# WE_1100_top.net
KiCad netlist of a schematic drawn in Altium Designer
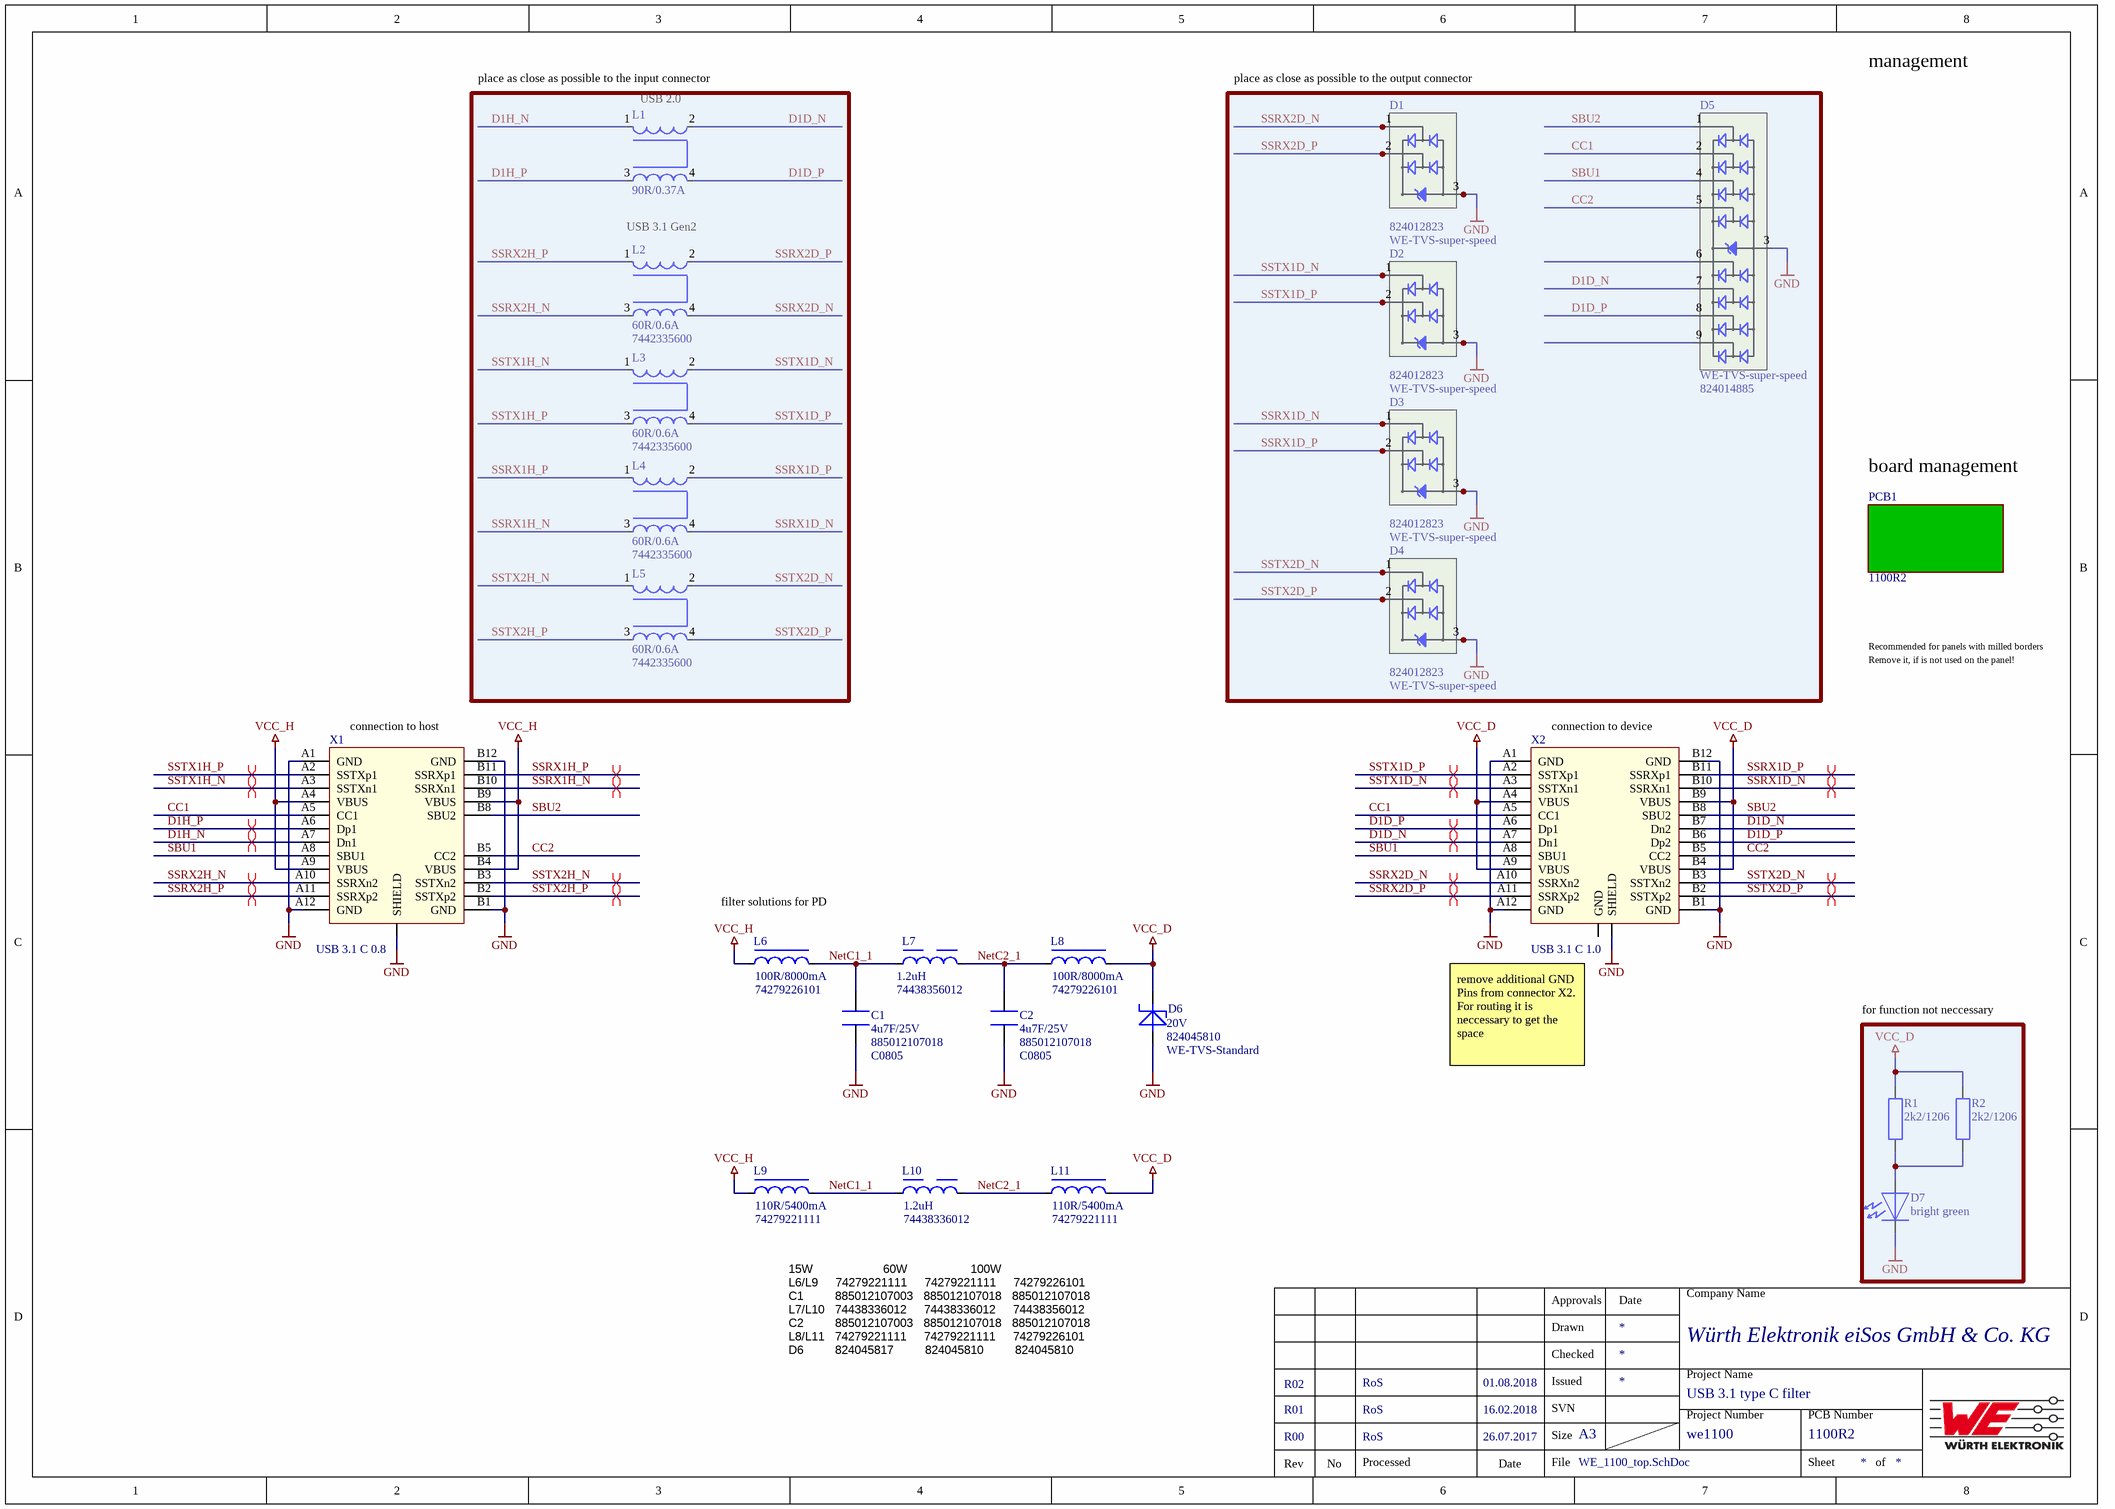
[diagram p0: WE_1100_top.SchDoc]

(export (version "E")
  (design (tool "Eeschema 10.0.6"))
  (components
    (comp (ref "C1")
      (value "4u7F/25V")
      (footprint "C0805 (reflow)")
      (description "Ceramic SMT X5R 4,7uF/25V 0805")
      (fields
        (field (name "ART.-CODE") "885012107018")
        (field (name "MANUFACTURER") "WE")
        (field (name "TOLERANCE") "20%")
        (field (name "CASE") "C0805")
      )
      (libsource (lib "capacitor") (part "4UF7/25-X5R-0805"))
    )
    (comp (ref "C2")
      (value "4u7F/25V")
      (footprint "C0805 (reflow)")
      (description "Ceramic SMT X5R 4,7uF/25V 0805")
      (fields
        (field (name "ART.-CODE") "885012107018")
        (field (name "MANUFACTURER") "WE")
        (field (name "TOLERANCE") "20%")
        (field (name "CASE") "C0805")
      )
      (libsource (lib "capacitor") (part "4UF7/25-X5R-0805"))
    )
    (comp (ref "D1")
      (value "WE-TVS-super-speed")
      (footprint "DFN88P100X50-6L")
      (description "TVS, diode, array, 2 channel ESD protection, 3.3V, DFN1012-6")
      (fields
        (field (name "MANUFACTURER") "WE")
        (field (name "VOLTAGE") "3.3V")
        (field (name "PART-NO.") "824012823")
      )
      (libsource (lib "rectifier") (part "WE-TVS-ULC-DFN1012-6"))
    )
    (comp (ref "D2")
      (value "WE-TVS-super-speed")
      (footprint "DFN88P100X50-6L")
      (description "TVS, diode, array, 2 channel ESD protection, 3.3V, DFN1012-6")
      (fields
        (field (name "MANUFACTURER") "WE")
        (field (name "VOLTAGE") "3.3V")
        (field (name "PART-NO.") "824012823")
      )
      (libsource (lib "rectifier") (part "WE-TVS-ULC-DFN1012-6"))
    )
    (comp (ref "D3")
      (value "WE-TVS-super-speed")
      (footprint "DFN88P100X50-6L")
      (description "TVS, diode, array, 2 channel ESD protection, 3.3V, DFN1012-6")
      (fields
        (field (name "MANUFACTURER") "WE")
        (field (name "VOLTAGE") "3.3V")
        (field (name "PART-NO.") "824012823")
      )
      (libsource (lib "rectifier") (part "WE-TVS-ULC-DFN1012-6"))
    )
    (comp (ref "D4")
      (value "WE-TVS-super-speed")
      (footprint "DFN88P100X50-6L")
      (description "TVS, diode, array, 2 channel ESD protection, 3.3V, DFN1012-6")
      (fields
        (field (name "MANUFACTURER") "WE")
        (field (name "VOLTAGE") "3.3V")
        (field (name "PART-NO.") "824012823")
      )
      (libsource (lib "rectifier") (part "WE-TVS-ULC-DFN1012-6"))
    )
    (comp (ref "D5")
      (value "WE-TVS-super-speed")
      (footprint "DFN90P380X55-9L")
      (description "TVS, diode, array, 8 channel ESD protection, 1.2V, DFN3810-9")
      (fields
        (field (name "MANUFACTURER") "WE")
        (field (name "VOLTAGE") "1.2V")
        (field (name "PART-NO.") "824014885")
      )
      (libsource (lib "rectifier") (part "WE-TVS-ULC-DFN3810"))
    )
    (comp (ref "D6")
      (value "WE-TVS-Standard")
      (footprint "DFN110P160X55-2L")
      (description "TVS, diode, unidir, ESD protection, 20V, DFN1610")
      (fields
        (field (name "MANUFACTURER") "WE")
        (field (name "VOLTAGE") "20V")
        (field (name "PART-NO.") "824045810")
      )
      (libsource (lib "rectifier") (part "WE-TVS20-ULC-DFN1610"))
    )
    (comp (ref "D7")
      (value "bright green")
      (footprint "LED-SMD-GR-2014X09L")
      (description "SMD-LED, Chipled 0805, brigth green")
      (fields (field (name "MANUFACTURER") "WE") (field (name "VOLTAGE") "2.0V"))
      (libsource (lib "optoelectronic") (part "LED Chipled VS 0805"))
    )
    (comp (ref "L1")
      (value "90R/0.37A")
      (footprint "WE-CNSW-0805 (REFLOW)")
      (description "Common mode line filter SMD WE-CNSW (USB, LVDS)")
      (fields
        (field (name "MANUFACTURER") "WE")
        (field (name "TOLERANCE") "25%")
        (field (name "HELPURL") "d:\\Hardware\\Datasheet\\Induktivitäten\\WE-CNSW\\744231091.pdf")
      )
      (libsource (lib "inductance") (part "Z90R-370mA-WE-CNSW"))
    )
    (comp (ref "L2")
      (value "60R/0.6A")
      (footprint "WE-CNSW-HF-0504 (REFLOW)")
      (description "Common mode line filter SMD WE-CNSW HF (USB3.0)")
      (fields
        (field (name "MANUFACTURER") "WE")
        (field (name "TOLERANCE") "25%")
        (field (name "PART-NO.") "7442335600")
        (field (name "HELPURL") "d:\\Hardware\\Datasheet\\Induktivitäten\\WE-CNSW_HF\\7442335600.pdf")
      )
      (libsource (lib "inductance") (part "Z60R-600mA-WE-CNSW HF"))
    )
    (comp (ref "L3")
      (value "60R/0.6A")
      (footprint "WE-CNSW-HF-0504 (REFLOW)")
      (description "Common mode line filter SMD WE-CNSW HF (USB3.0)")
      (fields
        (field (name "MANUFACTURER") "WE")
        (field (name "TOLERANCE") "25%")
        (field (name "PART-NO.") "7442335600")
        (field (name "HELPURL") "d:\\Hardware\\Datasheet\\Induktivitäten\\WE-CNSW_HF\\7442335600.pdf")
      )
      (libsource (lib "inductance") (part "Z60R-600mA-WE-CNSW HF"))
    )
    (comp (ref "L4")
      (value "60R/0.6A")
      (footprint "WE-CNSW-HF-0504 (REFLOW)")
      (description "Common mode line filter SMD WE-CNSW HF (USB3.0)")
      (fields
        (field (name "MANUFACTURER") "WE")
        (field (name "TOLERANCE") "25%")
        (field (name "PART-NO.") "7442335600")
        (field (name "HELPURL") "d:\\Hardware\\Datasheet\\Induktivitäten\\WE-CNSW_HF\\7442335600.pdf")
      )
      (libsource (lib "inductance") (part "Z60R-600mA-WE-CNSW HF"))
    )
    (comp (ref "L5")
      (value "60R/0.6A")
      (footprint "WE-CNSW-HF-0504 (REFLOW)")
      (description "Common mode line filter SMD WE-CNSW HF (USB3.0)")
      (fields
        (field (name "MANUFACTURER") "WE")
        (field (name "TOLERANCE") "25%")
        (field (name "PART-NO.") "7442335600")
        (field (name "HELPURL") "d:\\Hardware\\Datasheet\\Induktivitäten\\WE-CNSW_HF\\7442335600.pdf")
      )
      (libsource (lib "inductance") (part "Z60R-600mA-WE-CNSW HF"))
    )
    (comp (ref "L6")
      (value "100R/8000mA")
      (footprint "WE-MPSB_1812")
      (description "Multilayer Power Suppression Bead 1812 100R at 100MHz/0.006R")
      (fields
        (field (name "ART.-CODE") "74279226101")
        (field (name "MANUFACTURER") "WE")
        (field (name "TOLERANCE") "25%")
        (field (name "HELPURL") "d:\\Hardware\\Datasheet\\Induktivitäten\\Ferrit\\74279226101.pdf")
      )
      (libsource (lib "inductance") (part "Z100R_8000mA_1812_MPSB"))
    )
    (comp (ref "L7")
      (value "1.2uH")
      (footprint "WE-MAPI_4020")
      (description "Inductor SMT WE-MAPI 4020 1.2uH/5800mA")
      (fields
        (field (name "MANUFACTURER") "WE")
        (field (name "ART.-CODE") "74438356012")
        (field (name "TOLERANCE") "20%")
        (field (name "HELPURL") "d:\\Hardware\\Datasheet\\Induktivitäten\\WE-MAPI\\74438356012.pdf")
      )
      (libsource (lib "inductance") (part "1UH2-5.8A-SMD-WE-MAPI 4020"))
    )
    (comp (ref "L8")
      (value "100R/8000mA")
      (footprint "WE-MPSB_1812")
      (description "Multilayer Power Suppression Bead 1812 100R at 100MHz/0.006R")
      (fields
        (field (name "ART.-CODE") "74279226101")
        (field (name "MANUFACTURER") "WE")
        (field (name "TOLERANCE") "25%")
        (field (name "HELPURL") "d:\\Hardware\\Datasheet\\Induktivitäten\\Ferrit\\74279226101.pdf")
      )
      (libsource (lib "inductance") (part "Z100R_8000mA_1812_MPSB"))
    )
    (comp (ref "L9")
      (value "110R/5400mA")
      (footprint "WE-MPSB_1206")
      (description "Multilayer Power Suppression Bead 1206 110R at 100MHz/0.0095R")
      (fields
        (field (name "ART.-CODE") "74279221111")
        (field (name "MANUFACTURER") "WE")
        (field (name "TOLERANCE") "25%")
        (field (name "HELPURL") "d:\\Hardware\\Datasheet\\Induktivitäten\\Ferrit\\74279221111.pdf")
      )
      (libsource (lib "inductance") (part "Z110R_5400mA_1206_MPSB"))
    )
    (comp (ref "L10")
      (value "1.2uH")
      (footprint "WE-MAPI_3020")
      (description "Inductor SMT WE-MAPI 3020 1.2uH/3900mA")
      (fields
        (field (name "MANUFACTURER") "WE")
        (field (name "ART.-CODE") "74438336012")
        (field (name "TOLERANCE") "20%")
        (field (name "HELPURL") "d:\\Hardware\\Datasheet\\Induktivitäten\\WE-MAPI\\74438336012.pdf")
      )
      (libsource (lib "inductance") (part "1UH2-3.9A-SMD-WE-MAPI 3020"))
    )
    (comp (ref "L11")
      (value "110R/5400mA")
      (footprint "WE-MPSB_1206")
      (description "Multilayer Power Suppression Bead 1206 110R at 100MHz/0.0095R")
      (fields
        (field (name "ART.-CODE") "74279221111")
        (field (name "MANUFACTURER") "WE")
        (field (name "TOLERANCE") "25%")
        (field (name "HELPURL") "d:\\Hardware\\Datasheet\\Induktivitäten\\Ferrit\\74279221111.pdf")
      )
      (libsource (lib "inductance") (part "Z110R_5400mA_1206_MPSB"))
    )
    (comp (ref "PCB1")
      (value "1100R2")
      (description "only for partlist")
      (libsource (lib "misc") (part "PCB"))
    )
    (comp (ref "R1")
      (value "2k2/1206")
      (footprint "R1206 (reflow)")
      (description "Resistor 2K2 1% 1206 E24")
      (fields (field (name "POWER") "1/4W") (field (name "TOLERANCE") "1%"))
      (libsource (lib "resistor") (part "2K2-1-1206"))
    )
    (comp (ref "R2")
      (value "2k2/1206")
      (footprint "R1206 (reflow)")
      (description "Resistor 2K2 1% 1206 E24")
      (fields (field (name "POWER") "1/4W") (field (name "TOLERANCE") "1%"))
      (libsource (lib "resistor") (part "2K2-1-1206"))
    )
    (comp (ref "X1")
      (value "USB 3.1 C 0.8")
      (footprint "632712000011")
      (description "male USB 3.1 Type C 24 pins 90° THT & SMT LP 0.8")
      (fields (field (name "MANUFACTURER") "WE") (field (name "VOLTAGE") "20V"))
      (libsource (lib "connector") (part "ST-24 USB 3.1 C 0.8"))
    )
    (comp (ref "X2")
      (value "USB 3.1 C 1.0")
      (footprint "632723100011")
      (description "female USB 3.1 Type C 24 pins 90° THT & SMT LP 1.0")
      (fields (field (name "MANUFACTURER") "WE") (field (name "VOLTAGE") "20V"))
      (libsource (lib "connector") (part "BU-24 USB 3.1 C 1.0"))
    )
  )
  (nets
    (net (code "1") (name "/CC1") (class "Default")
      (node (ref "D5") (pin "2") (pinfunction "I/O2_2") (pintype "passive"))
      (node (ref "X1") (pin "A5") (pinfunction "CC1_A5") (pintype "passive"))
      (node (ref "X2") (pin "A5") (pinfunction "CC1_A5") (pintype "passive"))
    )
    (net (code "2") (name "/CC2") (class "Default")
      (node (ref "D5") (pin "5") (pinfunction "I/O4_5") (pintype "passive"))
      (node (ref "X1") (pin "B5") (pinfunction "CC2_B5") (pintype "passive"))
      (node (ref "X2") (pin "B5") (pinfunction "CC2_B5") (pintype "passive"))
    )
    (net (code "3") (name "/D1D_N") (class "Default")
      (node (ref "D5") (pin "7") (pinfunction "NC_7") (pintype "passive"))
      (node (ref "L1") (pin "2") (pintype "passive"))
      (node (ref "X2") (pin "A7") (pinfunction "Dn1_A7") (pintype "passive"))
      (node (ref "X2") (pin "B7") (pinfunction "Dn2_B7") (pintype "passive"))
    )
    (net (code "4") (name "/D1D_P") (class "Default")
      (node (ref "D5") (pin "8") (pinfunction "GND_8") (pintype "passive"))
      (node (ref "L1") (pin "4") (pintype "passive"))
      (node (ref "X2") (pin "A6") (pinfunction "Dp1_A6") (pintype "passive"))
      (node (ref "X2") (pin "B6") (pinfunction "Dp2_B6") (pintype "passive"))
    )
    (net (code "5") (name "/D1H_N") (class "Default")
      (node (ref "L1") (pin "1") (pintype "passive"))
      (node (ref "X1") (pin "A7") (pinfunction "Dn1_A7") (pintype "passive"))
    )
    (net (code "6") (name "/D1H_P") (class "Default")
      (node (ref "L1") (pin "3") (pintype "passive"))
      (node (ref "X1") (pin "A6") (pinfunction "Dp1_A6") (pintype "passive"))
    )
    (net (code "7") (name "/NetC1_1") (class "Default")
      (node (ref "C1") (pin "1") (pintype "passive"))
      (node (ref "L10") (pin "1") (pintype "passive"))
      (node (ref "L6") (pin "2") (pintype "passive"))
      (node (ref "L7") (pin "1") (pintype "passive"))
      (node (ref "L9") (pin "2") (pintype "passive"))
    )
    (net (code "8") (name "/NetC2_1") (class "Default")
      (node (ref "C2") (pin "1") (pintype "passive"))
      (node (ref "L10") (pin "2") (pintype "passive"))
      (node (ref "L11") (pin "1") (pintype "passive"))
      (node (ref "L7") (pin "2") (pintype "passive"))
      (node (ref "L8") (pin "1") (pintype "passive"))
    )
    (net (code "9") (name "/SBU1") (class "Default")
      (node (ref "D5") (pin "4") (pinfunction "I/O3_4") (pintype "passive"))
      (node (ref "X1") (pin "A8") (pinfunction "SBU1_A8") (pintype "passive"))
      (node (ref "X2") (pin "A8") (pinfunction "SBU1_A8") (pintype "passive"))
    )
    (net (code "10") (name "/SBU2") (class "Default")
      (node (ref "D5") (pin "1") (pinfunction "I/O1_1") (pintype "passive"))
      (node (ref "X1") (pin "B8") (pinfunction "SBU2_B8") (pintype "passive"))
      (node (ref "X2") (pin "B8") (pinfunction "SBU2_B8") (pintype "passive"))
    )
    (net (code "11") (name "/SSRX1D_N") (class "Default")
      (node (ref "D3") (pin "1") (pinfunction "I/O1_1") (pintype "passive"))
      (node (ref "D3") (pin "6") (pinfunction "I/O1_6") (pintype "passive"))
      (node (ref "L4") (pin "4") (pintype "passive"))
      (node (ref "X2") (pin "B10") (pinfunction "SSRXn1_B10") (pintype "passive"))
    )
    (net (code "12") (name "/SSRX1D_P") (class "Default")
      (node (ref "D3") (pin "2") (pinfunction "I/O2_2") (pintype "passive"))
      (node (ref "D3") (pin "5") (pinfunction "I/O2_5") (pintype "passive"))
      (node (ref "L4") (pin "2") (pintype "passive"))
      (node (ref "X2") (pin "B11") (pinfunction "SSRXp1_B11") (pintype "passive"))
    )
    (net (code "13") (name "/SSRX1H_N") (class "Default")
      (node (ref "L4") (pin "3") (pintype "passive"))
      (node (ref "X1") (pin "B10") (pinfunction "SSRXn1_B10") (pintype "passive"))
    )
    (net (code "14") (name "/SSRX1H_P") (class "Default")
      (node (ref "L4") (pin "1") (pintype "passive"))
      (node (ref "X1") (pin "B11") (pinfunction "SSRXp1_B11") (pintype "passive"))
    )
    (net (code "15") (name "/SSRX2D_N") (class "Default")
      (node (ref "D1") (pin "1") (pinfunction "I/O1_1") (pintype "passive"))
      (node (ref "D1") (pin "6") (pinfunction "I/O1_6") (pintype "passive"))
      (node (ref "L2") (pin "4") (pintype "passive"))
      (node (ref "X2") (pin "A10") (pinfunction "SSRXn2_A10") (pintype "passive"))
    )
    (net (code "16") (name "/SSRX2D_P") (class "Default")
      (node (ref "D1") (pin "2") (pinfunction "I/O2_2") (pintype "passive"))
      (node (ref "D1") (pin "5") (pinfunction "I/O2_5") (pintype "passive"))
      (node (ref "L2") (pin "2") (pintype "passive"))
      (node (ref "X2") (pin "A11") (pinfunction "SSRXp2_A11") (pintype "passive"))
    )
    (net (code "17") (name "/SSRX2H_N") (class "Default")
      (node (ref "L2") (pin "3") (pintype "passive"))
      (node (ref "X1") (pin "A10") (pinfunction "SSRXn2_A10") (pintype "passive"))
    )
    (net (code "18") (name "/SSRX2H_P") (class "Default")
      (node (ref "L2") (pin "1") (pintype "passive"))
      (node (ref "X1") (pin "A11") (pinfunction "SSRXp2_A11") (pintype "passive"))
    )
    (net (code "19") (name "/SSTX1D_N") (class "Default")
      (node (ref "D2") (pin "1") (pinfunction "I/O1_1") (pintype "passive"))
      (node (ref "D2") (pin "6") (pinfunction "I/O1_6") (pintype "passive"))
      (node (ref "L3") (pin "2") (pintype "passive"))
      (node (ref "X2") (pin "A3") (pinfunction "SSTXn1_A3") (pintype "passive"))
    )
    (net (code "20") (name "/SSTX1D_P") (class "Default")
      (node (ref "D2") (pin "2") (pinfunction "I/O2_2") (pintype "passive"))
      (node (ref "D2") (pin "5") (pinfunction "I/O2_5") (pintype "passive"))
      (node (ref "L3") (pin "4") (pintype "passive"))
      (node (ref "X2") (pin "A2") (pinfunction "SSTXp1_A2") (pintype "passive"))
    )
    (net (code "21") (name "/SSTX1H_N") (class "Default")
      (node (ref "L3") (pin "1") (pintype "passive"))
      (node (ref "X1") (pin "A3") (pinfunction "SSTXn1_A3") (pintype "passive"))
    )
    (net (code "22") (name "/SSTX1H_P") (class "Default")
      (node (ref "L3") (pin "3") (pintype "passive"))
      (node (ref "X1") (pin "A2") (pinfunction "SSTXp1_A2") (pintype "passive"))
    )
    (net (code "23") (name "/SSTX2D_N") (class "Default")
      (node (ref "D4") (pin "1") (pinfunction "I/O1_1") (pintype "passive"))
      (node (ref "D4") (pin "6") (pinfunction "I/O1_6") (pintype "passive"))
      (node (ref "L5") (pin "2") (pintype "passive"))
      (node (ref "X2") (pin "B3") (pinfunction "SSTXn2_B3") (pintype "passive"))
    )
    (net (code "24") (name "/SSTX2D_P") (class "Default")
      (node (ref "D4") (pin "2") (pinfunction "I/O2_2") (pintype "passive"))
      (node (ref "D4") (pin "5") (pinfunction "I/O2_5") (pintype "passive"))
      (node (ref "L5") (pin "4") (pintype "passive"))
      (node (ref "X2") (pin "B2") (pinfunction "SSTXp2_B2") (pintype "passive"))
    )
    (net (code "25") (name "/SSTX2H_N") (class "Default")
      (node (ref "L5") (pin "1") (pintype "passive"))
      (node (ref "X1") (pin "B3") (pinfunction "SSTXn2_B3") (pintype "passive"))
    )
    (net (code "26") (name "/SSTX2H_P") (class "Default")
      (node (ref "L5") (pin "3") (pintype "passive"))
      (node (ref "X1") (pin "B2") (pinfunction "SSTXp2_B2") (pintype "passive"))
    )
    (net (code "27") (name "GND") (class "Default")
      (node (ref "C1") (pin "2") (pintype "passive"))
      (node (ref "C2") (pin "2") (pintype "passive"))
      (node (ref "D1") (pin "3") (pinfunction "VDD_3") (pintype "passive"))
      (node (ref "D1") (pin "4") (pinfunction "VDD_4") (pintype "passive"))
      (node (ref "D2") (pin "3") (pinfunction "VDD_3") (pintype "passive"))
      (node (ref "D2") (pin "4") (pinfunction "VDD_4") (pintype "passive"))
      (node (ref "D3") (pin "3") (pinfunction "VDD_3") (pintype "passive"))
      (node (ref "D3") (pin "4") (pinfunction "VDD_4") (pintype "passive"))
      (node (ref "D4") (pin "3") (pinfunction "VDD_3") (pintype "passive"))
      (node (ref "D4") (pin "4") (pinfunction "VDD_4") (pintype "passive"))
      (node (ref "D5") (pin "3") (pinfunction "VDD_3") (pintype "passive"))
      (node (ref "D6") (pin "2") (pinfunction "I/O2_2") (pintype "passive"))
      (node (ref "D7") (pin "1") (pintype "passive"))
      (node (ref "X1") (pin "0") (pinfunction "SHIELD_0") (pintype "passive"))
      (node (ref "X1") (pin "A1") (pinfunction "GND_A1") (pintype "passive"))
      (node (ref "X1") (pin "A12") (pinfunction "GND_A12") (pintype "passive"))
      (node (ref "X1") (pin "B1") (pinfunction "GND_B1") (pintype "passive"))
      (node (ref "X1") (pin "B12") (pinfunction "GND_B12") (pintype "passive"))
      (node (ref "X2") (pin "0") (pinfunction "SHIELD_0") (pintype "passive"))
      (node (ref "X2") (pin "A1") (pinfunction "GND_A1") (pintype "passive"))
      (node (ref "X2") (pin "A12") (pinfunction "GND_A12") (pintype "passive"))
      (node (ref "X2") (pin "B1") (pinfunction "GND_B1") (pintype "passive"))
      (node (ref "X2") (pin "B12") (pinfunction "GND_B12") (pintype "passive"))
    )
    (net (code "28") (name "Net-(D7-Pad2)") (class "Default")
      (node (ref "D7") (pin "2") (pintype "passive"))
      (node (ref "R1") (pin "1") (pintype "passive"))
      (node (ref "R2") (pin "1") (pintype "passive"))
    )
    (net (code "29") (name "VCC_D") (class "Default")
      (node (ref "D6") (pin "1") (pinfunction "I/O1_1") (pintype "passive"))
      (node (ref "L11") (pin "2") (pintype "passive"))
      (node (ref "L8") (pin "2") (pintype "passive"))
      (node (ref "R1") (pin "2") (pintype "passive"))
      (node (ref "R2") (pin "2") (pintype "passive"))
      (node (ref "X2") (pin "A4") (pinfunction "VBUS_A4") (pintype "passive"))
      (node (ref "X2") (pin "A9") (pinfunction "VBUS_A9") (pintype "passive"))
      (node (ref "X2") (pin "B4") (pinfunction "VBUS_B4") (pintype "passive"))
      (node (ref "X2") (pin "B9") (pinfunction "VBUS_B9") (pintype "passive"))
    )
    (net (code "30") (name "VCC_H") (class "Default")
      (node (ref "L6") (pin "1") (pintype "passive"))
      (node (ref "L9") (pin "1") (pintype "passive"))
      (node (ref "X1") (pin "A4") (pinfunction "VBUS_A4") (pintype "passive"))
      (node (ref "X1") (pin "A9") (pinfunction "VBUS_A9") (pintype "passive"))
      (node (ref "X1") (pin "B4") (pinfunction "VBUS_B4") (pintype "passive"))
      (node (ref "X1") (pin "B9") (pinfunction "VBUS_B9") (pintype "passive"))
    )
    (net (code "31") (name "unconnected-(D5-NC-Pad6)") (class "Default")
      (node (ref "D5") (pin "6") (pinfunction "NC_6") (pintype "passive"))
    )
    (net (code "32") (name "unconnected-(D5-NC-Pad9)") (class "Default")
      (node (ref "D5") (pin "9") (pinfunction "NC_9") (pintype "passive"))
    )
    (net (code "33") (name "unconnected-(X2-PadGND)") (class "Default")
      (node (ref "X2") (pin "GND") (pinfunction "GND_GND") (pintype "passive"))
    )
  )
)
